# avrshift-uln2803.net
KiCad netlist of a schematic drawn in EAGLE
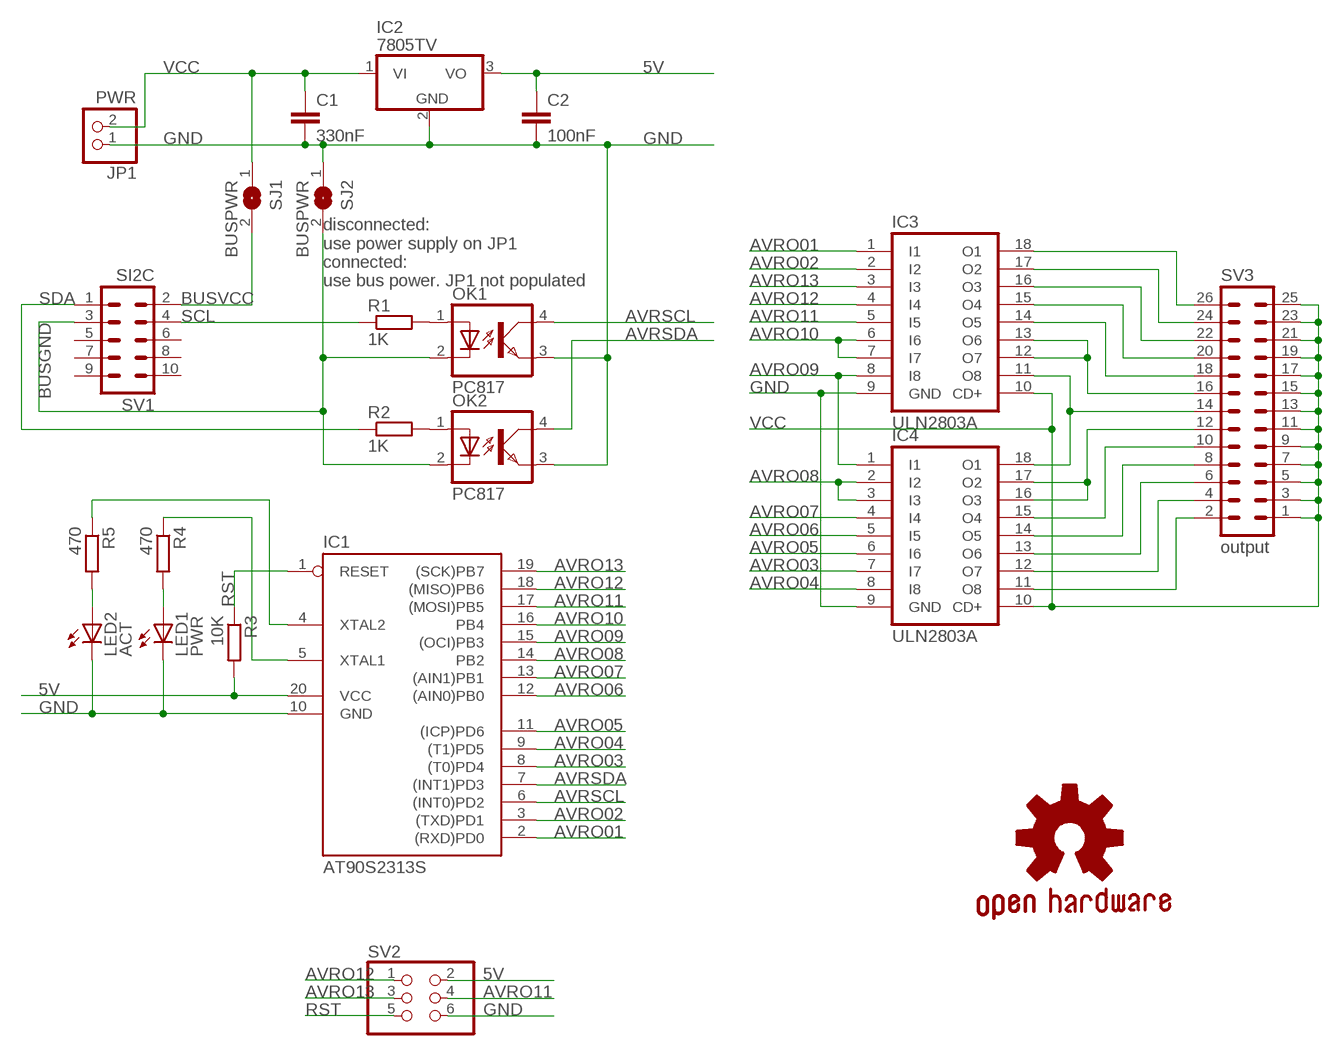
[diagram p0: schematic, sheet 1]

(export (version "E")
  (design (tool "Eeschema 10.0.6"))
  (components
    (comp (ref "C1")
      (value "330nF")
      (footprint "eagle-import:C2.5-3")
      (libsource (lib "eagle-import") (part "C2,5-3"))
    )
    (comp (ref "C2")
      (value "100nF")
      (footprint "eagle-import:C0805")
      (libsource (lib "eagle-import") (part "C-EUC0805"))
    )
    (comp (ref "GOLD_ORB_SM1")
      (value "OSHWLOGO_GOLD_ORB_SM")
      (footprint "eagle-import:OSHW2")
      (libsource (lib "eagle-import") (part "OSHWLOGO_GOLD_ORB_SM"))
    )
    (comp (ref "IC1")
      (value "AT90S2313S")
      (footprint "eagle-import:SO20L")
      (libsource (lib "eagle-import") (part "AT90S2313S"))
    )
    (comp (ref "IC2")
      (value "7805TV")
      (footprint "eagle-import:TO220V")
      (libsource (lib "eagle-import") (part "78TV05"))
    )
    (comp (ref "IC3")
      (value "ULN2803A")
      (footprint "eagle-import:DIL18")
      (libsource (lib "eagle-import") (part "ULN2803A"))
    )
    (comp (ref "IC4")
      (value "ULN2803A")
      (footprint "eagle-import:DIL18")
      (libsource (lib "eagle-import") (part "ULN2803A"))
    )
    (comp (ref "JP1")
      (value "PWR")
      (footprint "eagle-import:1X02")
      (libsource (lib "eagle-import") (part "PINHD-1X2"))
    )
    (comp (ref "LED1")
      (value "PWR")
      (footprint "eagle-import:SML0805")
      (libsource (lib "eagle-import") (part "LEDSML0805"))
    )
    (comp (ref "LED2")
      (value "ACT")
      (footprint "eagle-import:SML0805")
      (libsource (lib "eagle-import") (part "LEDSML0805"))
    )
    (comp (ref "OK1")
      (value "PC817")
      (footprint "eagle-import:DIL04")
      (fields (field (name "MPN") "PC817X4J000F"))
      (libsource (lib "eagle-import") (part "PC817"))
    )
    (comp (ref "OK2")
      (value "PC817")
      (footprint "eagle-import:DIL04")
      (fields (field (name "MPN") "PC817X4J000F"))
      (libsource (lib "eagle-import") (part "PC817"))
    )
    (comp (ref "R1")
      (value "1K")
      (footprint "eagle-import:R0805")
      (libsource (lib "eagle-import") (part "R-EU_R0805"))
    )
    (comp (ref "R2")
      (value "1K")
      (footprint "eagle-import:R0805")
      (libsource (lib "eagle-import") (part "R-EU_R0805"))
    )
    (comp (ref "R3")
      (value "10K")
      (footprint "eagle-import:R0805")
      (libsource (lib "eagle-import") (part "R-EU_R0805"))
    )
    (comp (ref "R4")
      (value "470")
      (footprint "eagle-import:R0805")
      (libsource (lib "eagle-import") (part "R-EU_R0805"))
    )
    (comp (ref "R5")
      (value "470")
      (footprint "eagle-import:R0805")
      (libsource (lib "eagle-import") (part "R-EU_R0805"))
    )
    (comp (ref "SJ1")
      (value "BUSPWR")
      (footprint "eagle-import:SJ")
      (libsource (lib "eagle-import") (part "SJ"))
    )
    (comp (ref "SJ2")
      (value "BUSPWR")
      (footprint "eagle-import:SJ")
      (libsource (lib "eagle-import") (part "SJ"))
    )
    (comp (ref "SV1")
      (value "SI2C")
      (footprint "eagle-import:ML10")
      (libsource (lib "eagle-import") (part "ML10"))
    )
    (comp (ref "SV2")
      (value "PINHD-2X3")
      (footprint "eagle-import:2X03")
      (libsource (lib "eagle-import") (part "PINHD-2X3"))
    )
    (comp (ref "SV3")
      (value "output")
      (footprint "eagle-import:ML26")
      (libsource (lib "eagle-import") (part "ML26"))
    )
  )
  (nets
    (net (code "1") (name "/5V") (class "Default")
      (node (ref "C2") (pin "1") (pinfunction "1_1") (pintype "passive"))
      (node (ref "IC1") (pin "20") (pinfunction "VCC_20") (pintype "power_in"))
      (node (ref "IC2") (pin "3") (pinfunction "VO_3") (pintype "passive"))
      (node (ref "R3") (pin "2") (pinfunction "2_2") (pintype "passive"))
      (node (ref "SV2") (pin "2") (pinfunction "2_2") (pintype "passive"))
    )
    (net (code "2") (name "/AVRO01") (class "Default")
      (node (ref "IC1") (pin "2") (pinfunction "(RXD)PD0_2") (pintype "bidirectional"))
      (node (ref "IC3") (pin "1") (pinfunction "I1_1") (pintype "input"))
    )
    (net (code "3") (name "/AVRO02") (class "Default")
      (node (ref "IC1") (pin "3") (pinfunction "(TXD)PD1_3") (pintype "bidirectional"))
      (node (ref "IC3") (pin "2") (pinfunction "I2_2") (pintype "input"))
    )
    (net (code "4") (name "/AVRO03") (class "Default")
      (node (ref "IC1") (pin "8") (pinfunction "(T0)PD4_8") (pintype "bidirectional"))
      (node (ref "IC4") (pin "7") (pinfunction "I7_7") (pintype "input"))
    )
    (net (code "5") (name "/AVRO04") (class "Default")
      (node (ref "IC1") (pin "9") (pinfunction "(T1)PD5_9") (pintype "bidirectional"))
      (node (ref "IC4") (pin "8") (pinfunction "I8_8") (pintype "input"))
    )
    (net (code "6") (name "/AVRO05") (class "Default")
      (node (ref "IC1") (pin "11") (pinfunction "(ICP)PD6_11") (pintype "bidirectional"))
      (node (ref "IC4") (pin "6") (pinfunction "I6_6") (pintype "input"))
    )
    (net (code "7") (name "/AVRO06") (class "Default")
      (node (ref "IC1") (pin "12") (pinfunction "(AIN0)PB0_12") (pintype "bidirectional"))
      (node (ref "IC4") (pin "5") (pinfunction "I5_5") (pintype "input"))
    )
    (net (code "8") (name "/AVRO07") (class "Default")
      (node (ref "IC1") (pin "13") (pinfunction "(AIN1)PB1_13") (pintype "bidirectional"))
      (node (ref "IC4") (pin "4") (pinfunction "I4_4") (pintype "input"))
    )
    (net (code "9") (name "/AVRO08") (class "Default")
      (node (ref "IC1") (pin "14") (pinfunction "PB2_14") (pintype "bidirectional"))
      (node (ref "IC4") (pin "2") (pinfunction "I2_2") (pintype "input"))
      (node (ref "IC4") (pin "3") (pinfunction "I3_3") (pintype "input"))
    )
    (net (code "10") (name "/AVRO09") (class "Default")
      (node (ref "IC1") (pin "15") (pinfunction "(OCI)PB3_15") (pintype "bidirectional"))
      (node (ref "IC3") (pin "8") (pinfunction "I8_8") (pintype "input"))
      (node (ref "IC4") (pin "1") (pinfunction "I1_1") (pintype "input"))
    )
    (net (code "11") (name "/AVRO10") (class "Default")
      (node (ref "IC1") (pin "16") (pinfunction "PB4_16") (pintype "bidirectional"))
      (node (ref "IC3") (pin "6") (pinfunction "I6_6") (pintype "input"))
      (node (ref "IC3") (pin "7") (pinfunction "I7_7") (pintype "input"))
    )
    (net (code "12") (name "/AVRO11") (class "Default")
      (node (ref "IC1") (pin "17") (pinfunction "(MOSI)PB5_17") (pintype "bidirectional"))
      (node (ref "IC3") (pin "5") (pinfunction "I5_5") (pintype "input"))
      (node (ref "SV2") (pin "4") (pinfunction "4_4") (pintype "passive"))
    )
    (net (code "13") (name "/AVRO12") (class "Default")
      (node (ref "IC1") (pin "18") (pinfunction "(MISO)PB6_18") (pintype "bidirectional"))
      (node (ref "IC3") (pin "4") (pinfunction "I4_4") (pintype "input"))
      (node (ref "SV2") (pin "1") (pinfunction "1_1") (pintype "passive"))
    )
    (net (code "14") (name "/AVRO13") (class "Default")
      (node (ref "IC1") (pin "19") (pinfunction "(SCK)PB7_19") (pintype "bidirectional"))
      (node (ref "IC3") (pin "3") (pinfunction "I3_3") (pintype "input"))
      (node (ref "SV2") (pin "3") (pinfunction "3_3") (pintype "passive"))
    )
    (net (code "15") (name "/AVRSCL") (class "Default")
      (node (ref "IC1") (pin "6") (pinfunction "(INT0)PD2_6") (pintype "bidirectional"))
      (node (ref "OK1") (pin "4") (pinfunction "COL_4") (pintype "passive"))
    )
    (net (code "16") (name "/AVRSDA") (class "Default")
      (node (ref "IC1") (pin "7") (pinfunction "(INT1)PD3_7") (pintype "bidirectional"))
      (node (ref "OK2") (pin "4") (pinfunction "COL_4") (pintype "passive"))
    )
    (net (code "17") (name "/BUSGND") (class "Default")
      (node (ref "OK1") (pin "2") (pinfunction "C_2") (pintype "passive"))
      (node (ref "OK2") (pin "2") (pinfunction "C_2") (pintype "passive"))
      (node (ref "SJ2") (pin "2") (pinfunction "2_2") (pintype "passive"))
      (node (ref "SV1") (pin "3") (pinfunction "3_3") (pintype "passive"))
    )
    (net (code "18") (name "/BUSVCC") (class "Default")
      (node (ref "SJ1") (pin "2") (pinfunction "2_2") (pintype "passive"))
      (node (ref "SV1") (pin "2") (pinfunction "2_2") (pintype "passive"))
    )
    (net (code "19") (name "/GND") (class "Default")
      (node (ref "C1") (pin "2") (pinfunction "2_2") (pintype "passive"))
      (node (ref "C2") (pin "2") (pinfunction "2_2") (pintype "passive"))
      (node (ref "IC1") (pin "10") (pinfunction "GND_10") (pintype "power_in"))
      (node (ref "IC2") (pin "2") (pinfunction "GND_2") (pintype "passive"))
      (node (ref "IC3") (pin "9") (pinfunction "GND_9") (pintype "power_in"))
      (node (ref "IC4") (pin "9") (pinfunction "GND_9") (pintype "power_in"))
      (node (ref "JP1") (pin "1") (pinfunction "1_1") (pintype "passive"))
      (node (ref "LED1") (pin "C") (pinfunction "C_C") (pintype "passive"))
      (node (ref "LED2") (pin "C") (pinfunction "C_C") (pintype "passive"))
      (node (ref "OK1") (pin "3") (pinfunction "EMIT_3") (pintype "passive"))
      (node (ref "OK2") (pin "3") (pinfunction "EMIT_3") (pintype "passive"))
      (node (ref "SJ2") (pin "1") (pinfunction "1_1") (pintype "passive"))
      (node (ref "SV2") (pin "6") (pinfunction "6_6") (pintype "passive"))
    )
    (net (code "20") (name "/RST") (class "Default")
      (node (ref "IC1") (pin "1") (pinfunction "RESET_1") (pintype "bidirectional"))
      (node (ref "R3") (pin "1") (pinfunction "1_1") (pintype "passive"))
      (node (ref "SV2") (pin "5") (pinfunction "5_5") (pintype "passive"))
    )
    (net (code "21") (name "/SCL") (class "Default")
      (node (ref "R1") (pin "1") (pinfunction "1_1") (pintype "passive"))
      (node (ref "SV1") (pin "4") (pinfunction "4_4") (pintype "passive"))
    )
    (net (code "22") (name "/SDA") (class "Default")
      (node (ref "R2") (pin "1") (pinfunction "1_1") (pintype "passive"))
      (node (ref "SV1") (pin "1") (pinfunction "1_1") (pintype "passive"))
    )
    (net (code "23") (name "/VCC") (class "Default")
      (node (ref "C1") (pin "1") (pinfunction "1_1") (pintype "passive"))
      (node (ref "IC2") (pin "1") (pinfunction "VI_1") (pintype "input"))
      (node (ref "IC3") (pin "10") (pinfunction "CD+_10") (pintype "passive"))
      (node (ref "IC4") (pin "10") (pinfunction "CD+_10") (pintype "passive"))
      (node (ref "JP1") (pin "2") (pinfunction "2_2") (pintype "passive"))
      (node (ref "SJ1") (pin "1") (pinfunction "1_1") (pintype "passive"))
      (node (ref "SV3") (pin "1") (pinfunction "1_1") (pintype "passive"))
      (node (ref "SV3") (pin "11") (pinfunction "11_11") (pintype "passive"))
      (node (ref "SV3") (pin "13") (pinfunction "13_13") (pintype "passive"))
      (node (ref "SV3") (pin "15") (pinfunction "15_15") (pintype "passive"))
      (node (ref "SV3") (pin "17") (pinfunction "17_17") (pintype "passive"))
      (node (ref "SV3") (pin "19") (pinfunction "19_19") (pintype "passive"))
      (node (ref "SV3") (pin "21") (pinfunction "21_21") (pintype "passive"))
      (node (ref "SV3") (pin "23") (pinfunction "23_23") (pintype "passive"))
      (node (ref "SV3") (pin "25") (pinfunction "25_25") (pintype "passive"))
      (node (ref "SV3") (pin "3") (pinfunction "3_3") (pintype "passive"))
      (node (ref "SV3") (pin "5") (pinfunction "5_5") (pintype "passive"))
      (node (ref "SV3") (pin "7") (pinfunction "7_7") (pintype "passive"))
      (node (ref "SV3") (pin "9") (pinfunction "9_9") (pintype "passive"))
    )
    (net (code "24") (name "Net-(IC1-XTAL1)") (class "Default")
      (node (ref "IC1") (pin "5") (pinfunction "XTAL1_5") (pintype "bidirectional"))
      (node (ref "R4") (pin "1") (pinfunction "1_1") (pintype "passive"))
    )
    (net (code "25") (name "Net-(IC1-XTAL2)") (class "Default")
      (node (ref "IC1") (pin "4") (pinfunction "XTAL2_4") (pintype "bidirectional"))
      (node (ref "R5") (pin "1") (pinfunction "1_1") (pintype "passive"))
    )
    (net (code "26") (name "Net-(IC3-O1)") (class "Default")
      (node (ref "IC3") (pin "18") (pinfunction "O1_18") (pintype "open_collector"))
      (node (ref "SV3") (pin "26") (pinfunction "26_26") (pintype "passive"))
    )
    (net (code "27") (name "Net-(IC3-O2)") (class "Default")
      (node (ref "IC3") (pin "17") (pinfunction "O2_17") (pintype "open_collector"))
      (node (ref "SV3") (pin "24") (pinfunction "24_24") (pintype "passive"))
    )
    (net (code "28") (name "Net-(IC3-O3)") (class "Default")
      (node (ref "IC3") (pin "16") (pinfunction "O3_16") (pintype "open_collector"))
      (node (ref "SV3") (pin "22") (pinfunction "22_22") (pintype "passive"))
    )
    (net (code "29") (name "Net-(IC3-O4)") (class "Default")
      (node (ref "IC3") (pin "15") (pinfunction "O4_15") (pintype "open_collector"))
      (node (ref "SV3") (pin "20") (pinfunction "20_20") (pintype "passive"))
    )
    (net (code "30") (name "Net-(IC3-O5)") (class "Default")
      (node (ref "IC3") (pin "14") (pinfunction "O5_14") (pintype "open_collector"))
      (node (ref "SV3") (pin "18") (pinfunction "18_18") (pintype "passive"))
    )
    (net (code "31") (name "Net-(IC3-O6)") (class "Default")
      (node (ref "IC3") (pin "12") (pinfunction "O7_12") (pintype "open_collector"))
      (node (ref "IC3") (pin "13") (pinfunction "O6_13") (pintype "open_collector"))
      (node (ref "SV3") (pin "16") (pinfunction "16_16") (pintype "passive"))
    )
    (net (code "32") (name "Net-(IC3-O8)") (class "Default")
      (node (ref "IC3") (pin "11") (pinfunction "O8_11") (pintype "open_collector"))
      (node (ref "IC4") (pin "18") (pinfunction "O1_18") (pintype "open_collector"))
      (node (ref "SV3") (pin "14") (pinfunction "14_14") (pintype "passive"))
    )
    (net (code "33") (name "Net-(IC4-O2)") (class "Default")
      (node (ref "IC4") (pin "16") (pinfunction "O3_16") (pintype "open_collector"))
      (node (ref "IC4") (pin "17") (pinfunction "O2_17") (pintype "open_collector"))
      (node (ref "SV3") (pin "12") (pinfunction "12_12") (pintype "passive"))
    )
    (net (code "34") (name "Net-(IC4-O4)") (class "Default")
      (node (ref "IC4") (pin "15") (pinfunction "O4_15") (pintype "open_collector"))
      (node (ref "SV3") (pin "10") (pinfunction "10_10") (pintype "passive"))
    )
    (net (code "35") (name "Net-(IC4-O5)") (class "Default")
      (node (ref "IC4") (pin "14") (pinfunction "O5_14") (pintype "open_collector"))
      (node (ref "SV3") (pin "8") (pinfunction "8_8") (pintype "passive"))
    )
    (net (code "36") (name "Net-(IC4-O6)") (class "Default")
      (node (ref "IC4") (pin "13") (pinfunction "O6_13") (pintype "open_collector"))
      (node (ref "SV3") (pin "6") (pinfunction "6_6") (pintype "passive"))
    )
    (net (code "37") (name "Net-(IC4-O7)") (class "Default")
      (node (ref "IC4") (pin "12") (pinfunction "O7_12") (pintype "open_collector"))
      (node (ref "SV3") (pin "4") (pinfunction "4_4") (pintype "passive"))
    )
    (net (code "38") (name "Net-(IC4-O8)") (class "Default")
      (node (ref "IC4") (pin "11") (pinfunction "O8_11") (pintype "open_collector"))
      (node (ref "SV3") (pin "2") (pinfunction "2_2") (pintype "passive"))
    )
    (net (code "39") (name "Net-(LED1-PadA)") (class "Default")
      (node (ref "LED1") (pin "A") (pinfunction "A_A") (pintype "passive"))
      (node (ref "R4") (pin "2") (pinfunction "2_2") (pintype "passive"))
    )
    (net (code "40") (name "Net-(LED2-PadA)") (class "Default")
      (node (ref "LED2") (pin "A") (pinfunction "A_A") (pintype "passive"))
      (node (ref "R5") (pin "2") (pinfunction "2_2") (pintype "passive"))
    )
    (net (code "41") (name "Net-(OK1-A)") (class "Default")
      (node (ref "OK1") (pin "1") (pinfunction "A_1") (pintype "passive"))
      (node (ref "R1") (pin "2") (pinfunction "2_2") (pintype "passive"))
    )
    (net (code "42") (name "Net-(OK2-A)") (class "Default")
      (node (ref "OK2") (pin "1") (pinfunction "A_1") (pintype "passive"))
      (node (ref "R2") (pin "2") (pinfunction "2_2") (pintype "passive"))
    )
    (net (code "43") (name "unconnected-(SV1-Pad5)") (class "Default")
      (node (ref "SV1") (pin "5") (pinfunction "5_5") (pintype "passive"))
    )
    (net (code "44") (name "unconnected-(SV1-Pad6)") (class "Default")
      (node (ref "SV1") (pin "6") (pinfunction "6_6") (pintype "passive"))
    )
    (net (code "45") (name "unconnected-(SV1-Pad7)") (class "Default")
      (node (ref "SV1") (pin "7") (pinfunction "7_7") (pintype "passive"))
    )
    (net (code "46") (name "unconnected-(SV1-Pad8)") (class "Default")
      (node (ref "SV1") (pin "8") (pinfunction "8_8") (pintype "passive"))
    )
    (net (code "47") (name "unconnected-(SV1-Pad9)") (class "Default")
      (node (ref "SV1") (pin "9") (pinfunction "9_9") (pintype "passive"))
    )
    (net (code "48") (name "unconnected-(SV1-Pad10)") (class "Default")
      (node (ref "SV1") (pin "10") (pinfunction "10_10") (pintype "passive"))
    )
  )
)
